# ProProject___2024-07-08.net
KiCad netlist of a schematic drawn in EasyEDA Pro
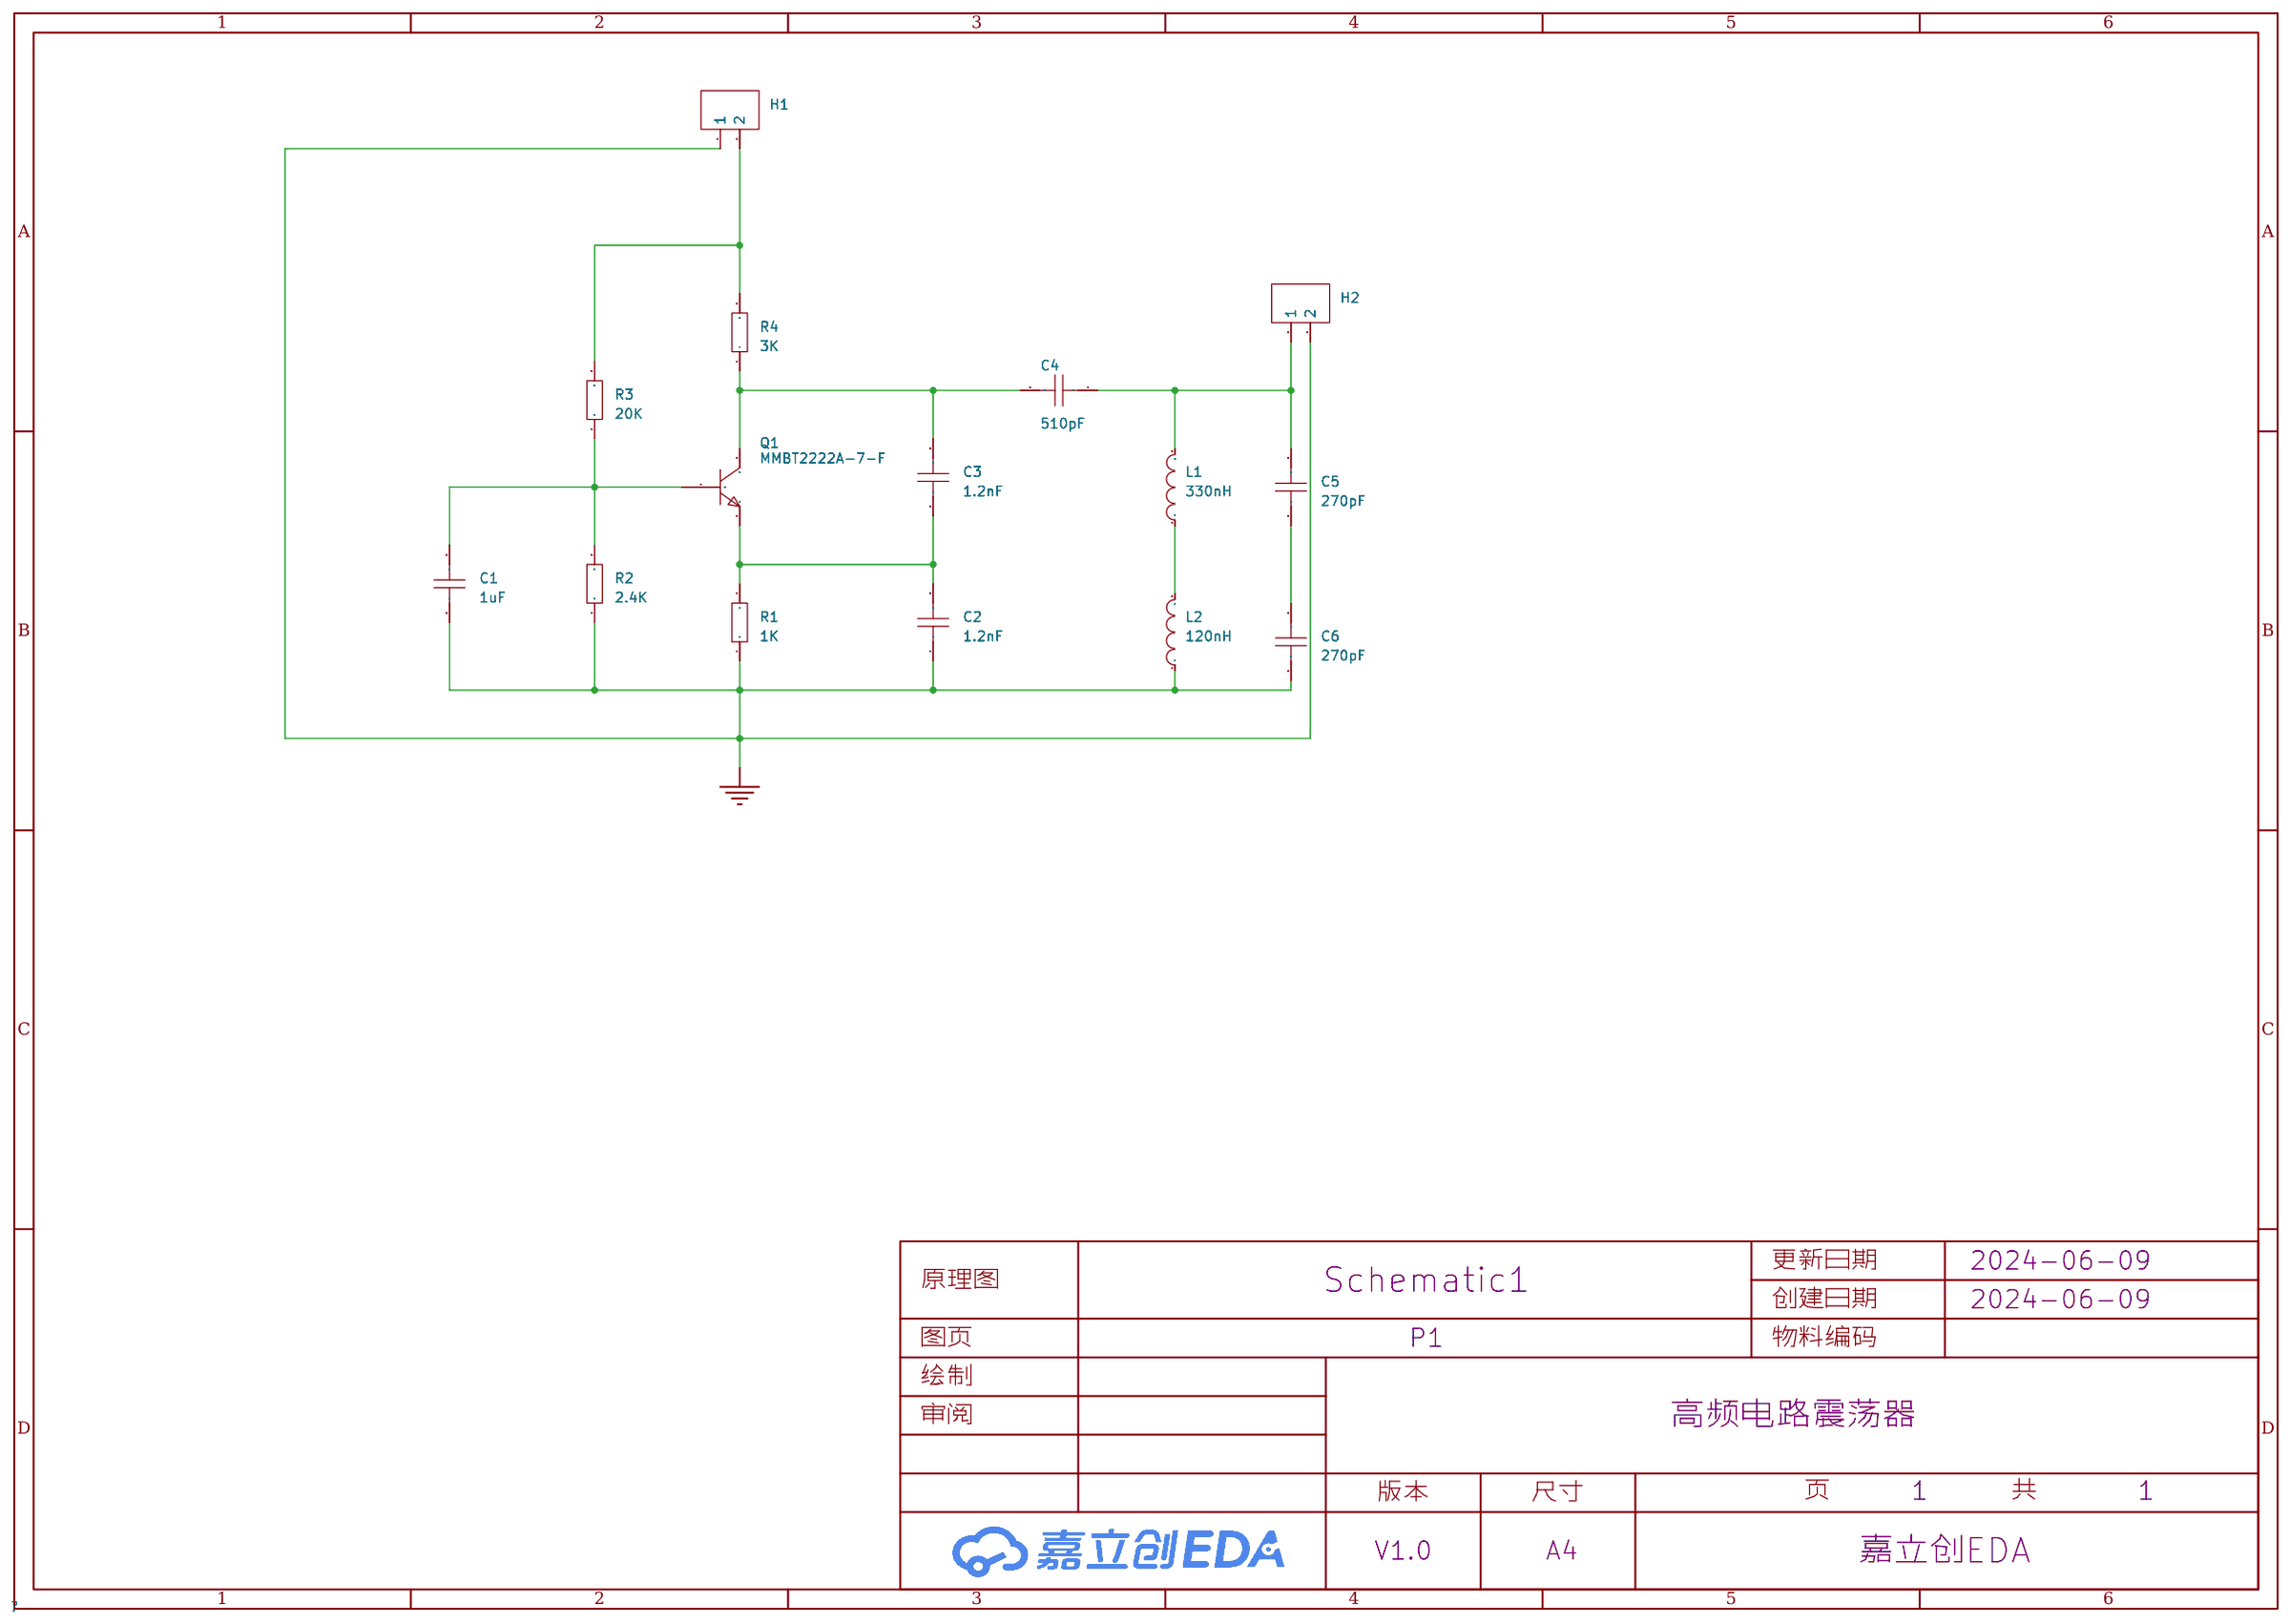
[diagram p0: schematic sheet]

(export (version "E")
  (design (tool "Eeschema 10.0.6"))
  (components
    (comp (ref "C1")
      (value "1uF")
      (footprint "easyedapro:C0805")
      (libsource (lib "easyedapro") (part "CapAcitance"))
    )
    (comp (ref "C2")
      (value "1.2nF")
      (footprint "easyedapro:C0805")
      (libsource (lib "easyedapro") (part "CapAcitance"))
    )
    (comp (ref "C3")
      (value "1.2nF")
      (footprint "easyedapro:C0805")
      (libsource (lib "easyedapro") (part "CapAcitance"))
    )
    (comp (ref "C4")
      (value "510pF")
      (footprint "easyedapro:C0805")
      (libsource (lib "easyedapro") (part "CapAcitance"))
    )
    (comp (ref "C5")
      (value "270pF")
      (footprint "easyedapro:C0805")
      (libsource (lib "easyedapro") (part "CapAcitance"))
    )
    (comp (ref "C6")
      (value "270pF")
      (footprint "easyedapro:C0805")
      (libsource (lib "easyedapro") (part "CapAcitance"))
    )
    (comp (ref "H1")
      (value "~")
      (footprint "easyedapro:HDR-TH_2P-P2.54-V-F")
      (libsource (lib "easyedapro") (part "Header-Female-2.54_1x2"))
    )
    (comp (ref "H2")
      (value "~")
      (footprint "easyedapro:HDR-TH_2P-P2.54-V-F")
      (libsource (lib "easyedapro") (part "Header-Female-2.54_1x2"))
    )
    (comp (ref "L1")
      (value "330nH")
      (footprint "easyedapro:L0805")
      (libsource (lib "easyedapro") (part "SDFL2012S100KTF"))
    )
    (comp (ref "L2")
      (value "120nH")
      (footprint "easyedapro:L0805")
      (libsource (lib "easyedapro") (part "SDFL2012S100KTF"))
    )
    (comp (ref "Q1")
      (value "MMBT2222A-7-F")
      (footprint "easyedapro:SOT-23-3_L2.9-W1.6-P1.90-LS2.8-BR")
      (description "晶体管类型:NPN;集电极电流(Ic):600mA;集射极击穿电压(Vceo):40V;功率(Pd):310mW;直流电流增益(hFE@Ic,Vce):100@150mA,10V;")
      (fields (field (name "Manufacturer") "DIODES(美台)"))
      (libsource (lib "easyedapro") (part "MMBT2222A-7-F"))
    )
    (comp (ref "R1") (value "1K") (footprint "easyedapro:R0805") (libsource (lib "easyedapro") (part "电阻")))
    (comp (ref "R2") (value "2.4K") (footprint "easyedapro:R0805") (libsource (lib "easyedapro") (part "电阻")))
    (comp (ref "R3") (value "20K") (footprint "easyedapro:R0805") (libsource (lib "easyedapro") (part "电阻")))
    (comp (ref "R4") (value "3K") (footprint "easyedapro:R0805") (libsource (lib "easyedapro") (part "电阻")))
  )
  (nets
    (net (code "1") (name "GND") (class "Default")
      (node (ref "C1") (pin "2") (pinfunction "2_2") (pintype "input"))
      (node (ref "C2") (pin "1") (pinfunction "1_1") (pintype "input"))
      (node (ref "C6") (pin "1") (pinfunction "1_1") (pintype "input"))
      (node (ref "H1") (pin "1") (pinfunction "1_1") (pintype "input"))
      (node (ref "H2") (pin "2") (pinfunction "2_2") (pintype "input"))
      (node (ref "L2") (pin "1") (pinfunction "1_1") (pintype "input"))
      (node (ref "R1") (pin "1") (pinfunction "1_1") (pintype "input"))
      (node (ref "R2") (pin "1") (pinfunction "1_1") (pintype "input"))
    )
    (net (code "2") (name "Net-(C4-Pad1)") (class "Default")
      (node (ref "C4") (pin "1") (pinfunction "1_1") (pintype "input"))
      (node (ref "C5") (pin "2") (pinfunction "2_2") (pintype "input"))
      (node (ref "H2") (pin "1") (pinfunction "1_1") (pintype "input"))
      (node (ref "L1") (pin "2") (pinfunction "2_2") (pintype "input"))
    )
    (net (code "3") (name "Net-(C5-Pad1)") (class "Default")
      (node (ref "C5") (pin "1") (pinfunction "1_1") (pintype "input"))
      (node (ref "C6") (pin "2") (pinfunction "2_2") (pintype "input"))
    )
    (net (code "4") (name "Net-(H1-Pad2)") (class "Default")
      (node (ref "H1") (pin "2") (pinfunction "2_2") (pintype "input"))
      (node (ref "R3") (pin "2") (pinfunction "2_2") (pintype "input"))
      (node (ref "R4") (pin "2") (pinfunction "2_2") (pintype "input"))
    )
    (net (code "5") (name "Net-(L1-Pad1)") (class "Default")
      (node (ref "L1") (pin "1") (pinfunction "1_1") (pintype "input"))
      (node (ref "L2") (pin "2") (pinfunction "2_2") (pintype "input"))
    )
    (net (code "6") (name "Net-(Q1-B)") (class "Default")
      (node (ref "C1") (pin "1") (pinfunction "1_1") (pintype "input"))
      (node (ref "Q1") (pin "1") (pinfunction "B_1") (pintype "unspecified"))
      (node (ref "R2") (pin "2") (pinfunction "2_2") (pintype "input"))
      (node (ref "R3") (pin "1") (pinfunction "1_1") (pintype "input"))
    )
    (net (code "7") (name "Net-(Q1-C)") (class "Default")
      (node (ref "C3") (pin "2") (pinfunction "2_2") (pintype "input"))
      (node (ref "C4") (pin "2") (pinfunction "2_2") (pintype "input"))
      (node (ref "Q1") (pin "3") (pinfunction "C_3") (pintype "unspecified"))
      (node (ref "R4") (pin "1") (pinfunction "1_1") (pintype "input"))
    )
    (net (code "8") (name "Net-(Q1-E)") (class "Default")
      (node (ref "C2") (pin "2") (pinfunction "2_2") (pintype "input"))
      (node (ref "C3") (pin "1") (pinfunction "1_1") (pintype "input"))
      (node (ref "Q1") (pin "2") (pinfunction "E_2") (pintype "unspecified"))
      (node (ref "R1") (pin "2") (pinfunction "2_2") (pintype "input"))
    )
  )
)
